# MCU-Board.net
KiCad netlist of a schematic drawn in Altium Designer
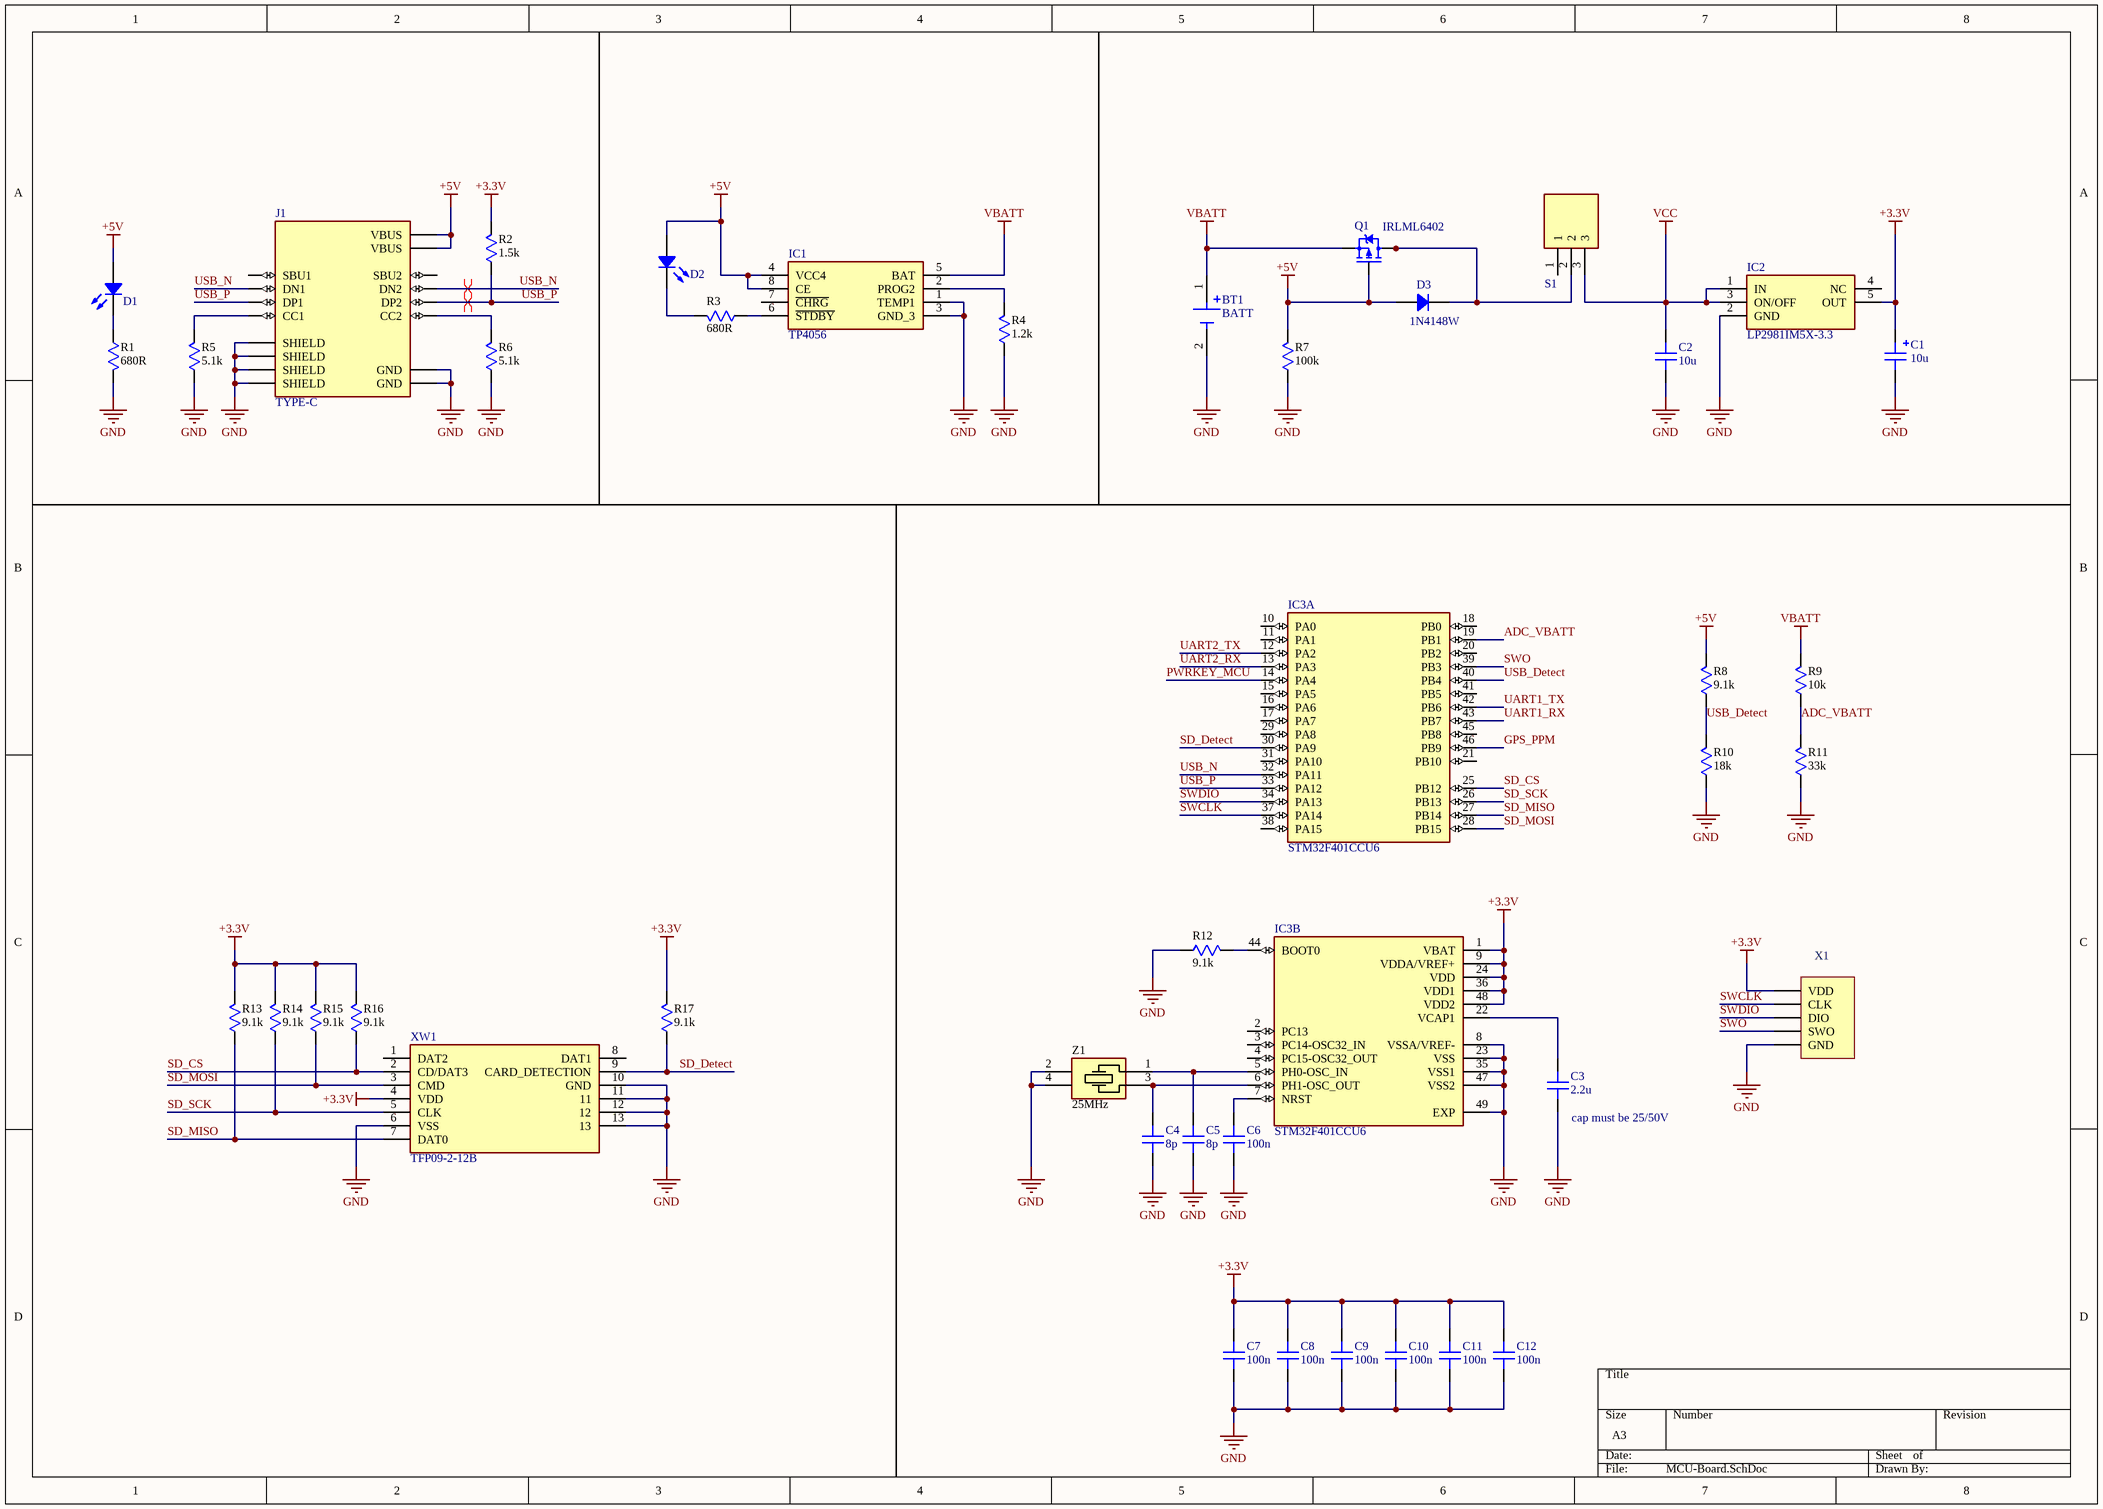
[diagram p0: MCU-Board.SchDoc]

(export (version "E")
  (design (tool "Eeschema 10.0.6"))
  (components
    (comp (ref "BT1")
      (value "BATT")
      (footprint "CON: HOLDER 18650 x1")
      (description "BATTERY")
      (fields (field (name "MP") "BH123A") (field (name "MF") "MPD"))
      (libsource (lib "Schlib") (part "BATT"))
    )
    (comp (ref "C1")
      (value "10u")
      (footprint "PcbLib:CAP: TANTAL-A")
      (description "SMD Capacitor Polar")
      (libsource (lib "Schlib") (part "Capacitor_polar"))
    )
    (comp (ref "C2")
      (value "10u")
      (footprint "PcbLib:CAP: 0805")
      (description "SMD Capacitor")
      (libsource (lib "Schlib") (part "Capacitor"))
    )
    (comp (ref "C3")
      (value "2.2u")
      (footprint "PcbLib:CAP: 0805")
      (description "SMD Capacitor")
      (libsource (lib "Schlib") (part "Capacitor"))
    )
    (comp (ref "C4")
      (value "8p")
      (footprint "PcbLib:CAP: 0603")
      (description "SMD Capacitor")
      (libsource (lib "Schlib") (part "Capacitor"))
    )
    (comp (ref "C5")
      (value "8p")
      (footprint "PcbLib:CAP: 0603")
      (description "SMD Capacitor")
      (libsource (lib "Schlib") (part "Capacitor"))
    )
    (comp (ref "C6")
      (value "100n")
      (footprint "PcbLib:CAP: 0603")
      (description "SMD Capacitor")
      (libsource (lib "Schlib") (part "Capacitor"))
    )
    (comp (ref "C7")
      (value "100n")
      (footprint "PcbLib:CAP: 0603")
      (description "SMD Capacitor")
      (libsource (lib "Schlib") (part "Capacitor"))
    )
    (comp (ref "C8")
      (value "100n")
      (footprint "PcbLib:CAP: 0603")
      (description "SMD Capacitor")
      (libsource (lib "Schlib") (part "Capacitor"))
    )
    (comp (ref "C9")
      (value "100n")
      (footprint "PcbLib:CAP: 0603")
      (description "SMD Capacitor")
      (libsource (lib "Schlib") (part "Capacitor"))
    )
    (comp (ref "C10")
      (value "100n")
      (footprint "PcbLib:CAP: 0603")
      (description "SMD Capacitor")
      (libsource (lib "Schlib") (part "Capacitor"))
    )
    (comp (ref "C11")
      (value "100n")
      (footprint "PcbLib:CAP: 0603")
      (description "SMD Capacitor")
      (libsource (lib "Schlib") (part "Capacitor"))
    )
    (comp (ref "C12")
      (value "100n")
      (footprint "PcbLib:CAP: 0603")
      (description "SMD Capacitor")
      (libsource (lib "Schlib") (part "Capacitor"))
    )
    (comp (ref "D1")
      (value "~")
      (footprint "PcbLib:LED 0603_1608")
      (description "Chip LED")
      (libsource (lib "Schlib") (part "LED"))
    )
    (comp (ref "D2")
      (value "~")
      (footprint "PcbLib:LED 0603_1608")
      (description "Chip LED")
      (libsource (lib "Schlib") (part "LED"))
    )
    (comp (ref "D3")
      (value "1N4148W")
      (footprint "DIODE: SOD123")
      (description "Rectifier Diode")
      (libsource (lib "Schlib") (part "Diode"))
    )
    (comp (ref "IC1")
      (value "TP4056")
      (footprint "PcbLib:SOIC127P600X175-9N")
      (description "Connector")
      (libsource (lib "Schlib") (part "TP4056"))
    )
    (comp (ref "IC2")
      (value "LP2981IM5X-3.3")
      (footprint "PcbLib:SOT95P280X145-5N")
      (description "Integrated Circuit")
      (fields
        (field (name "MANUFACTURER_PART_NUMBER") "LP2981IM5X-5.0")
        (field (name "MOUSER PART NUMBER") "926-LP2981IM5X-50")
      )
      (libsource (lib "Schlib") (part "LP2981IM5X-3.3"))
    )
    (comp (ref "IC3")
      (value "STM32F401CCU6")
      (footprint "PcbLib:QFN50P700X700X60-49N-D")
      (description "Integrated Circuit")
      (fields (field (name "MOUSER PART NUMBER") "511-STM32F401CCU6"))
      (libsource (lib "Schlib") (part "STM32F401CCU6"))
    )
    (comp (ref "J1")
      (value "TYPE-C")
      (footprint "PcbLib:HRO_TYPE-C-31-M-12")
      (description "USB Connectors 24 Receptacle 1 8.94*7.3mm RoHS")
      (fields (field (name "MP") "TYPE-C-31-M-12"))
      (libsource (lib "Schlib") (part "TYPE-C-31-M-12"))
    )
    (comp (ref "Q1")
      (value "IRLML6402")
      (footprint "SOT95P280X130-6N")
      (description "P-Channel Enhancement Mode MOSFET")
      (libsource (lib "Schlib") (part "MOSP_IRLMLS6802_SOT23"))
    )
    (comp (ref "R1")
      (value "680R")
      (footprint "PcbLib:RES: 0603")
      (fields
        (field (name "MANUFACTURER") "Yageo")
        (field (name "PARTNUMBER") "RC0201JR-07100RL")
        (field (name "VALUEMANUFACTURERPARTNUMBER") "Resistor film, 680R, , 0201, 0.05W, -55...+125°C")
      )
      (libsource (lib "Schlib") (part "Resistor"))
    )
    (comp (ref "R2")
      (value "1.5k")
      (footprint "PcbLib:RES: 0603")
      (fields
        (field (name "MANUFACTURER") "Yageo")
        (field (name "PARTNUMBER") "RC0201JR-07100RL")
        (field (name "VALUEMANUFACTURERPARTNUMBER") "Resistor film, 1.5k, , 0201, 0.05W, -55...+125°C")
      )
      (libsource (lib "Schlib") (part "Resistor"))
    )
    (comp (ref "R3")
      (value "680R")
      (footprint "PcbLib:RES: 0603")
      (fields
        (field (name "MANUFACTURER") "Yageo")
        (field (name "PARTNUMBER") "RC0201JR-07100RL")
        (field (name "VALUEMANUFACTURERPARTNUMBER") "Resistor film, 680R, , 0201, 0.05W, -55...+125°C")
      )
      (libsource (lib "Schlib") (part "Resistor"))
    )
    (comp (ref "R4")
      (value "1.2k")
      (footprint "PcbLib:RES: 0805")
      (fields
        (field (name "MANUFACTURER") "Yageo")
        (field (name "PARTNUMBER") "RC0201JR-07100RL")
        (field (name "VALUEMANUFACTURERPARTNUMBER") "Resistor film, 1.2k, , 0201, 0.05W, -55...+125°C")
      )
      (libsource (lib "Schlib") (part "Resistor"))
    )
    (comp (ref "R5")
      (value "5.1k")
      (footprint "PcbLib:RES: 0603")
      (fields
        (field (name "MANUFACTURER") "Yageo")
        (field (name "PARTNUMBER") "RC0201JR-07100RL")
        (field (name "VALUEMANUFACTURERPARTNUMBER") "Resistor film, 5.1k, , 0201, 0.05W, -55...+125°C")
      )
      (libsource (lib "Schlib") (part "Resistor"))
    )
    (comp (ref "R6")
      (value "5.1k")
      (footprint "PcbLib:RES: 0603")
      (fields
        (field (name "MANUFACTURER") "Yageo")
        (field (name "PARTNUMBER") "RC0201JR-07100RL")
        (field (name "VALUEMANUFACTURERPARTNUMBER") "Resistor film, 5.1k, , 0201, 0.05W, -55...+125°C")
      )
      (libsource (lib "Schlib") (part "Resistor"))
    )
    (comp (ref "R7")
      (value "100k")
      (footprint "PcbLib:RES: 0603")
      (fields
        (field (name "MANUFACTURER") "Yageo")
        (field (name "PARTNUMBER") "RC0201JR-07100RL")
        (field (name "VALUEMANUFACTURERPARTNUMBER") "Resistor film, 100k, , 0201, 0.05W, -55...+125°C")
      )
      (libsource (lib "Schlib") (part "Resistor"))
    )
    (comp (ref "R8")
      (value "9.1k")
      (footprint "PcbLib:RES: 0603")
      (fields
        (field (name "MANUFACTURER") "Yageo")
        (field (name "PARTNUMBER") "RC0201JR-07100RL")
        (field (name "VALUEMANUFACTURERPARTNUMBER") "Resistor film, 9.1k, , 0201, 0.05W, -55...+125°C")
      )
      (libsource (lib "Schlib") (part "Resistor"))
    )
    (comp (ref "R9")
      (value "10k")
      (footprint "PcbLib:RES: 0603")
      (fields
        (field (name "MANUFACTURER") "Yageo")
        (field (name "PARTNUMBER") "RC0201JR-07100RL")
        (field (name "VALUEMANUFACTURERPARTNUMBER") "Resistor film, 10k, , 0201, 0.05W, -55...+125°C")
      )
      (libsource (lib "Schlib") (part "Resistor"))
    )
    (comp (ref "R10")
      (value "18k")
      (footprint "PcbLib:RES: 0603")
      (fields
        (field (name "MANUFACTURER") "Yageo")
        (field (name "PARTNUMBER") "RC0201JR-07100RL")
        (field (name "VALUEMANUFACTURERPARTNUMBER") "Resistor film, 18k, , 0201, 0.05W, -55...+125°C")
      )
      (libsource (lib "Schlib") (part "Resistor"))
    )
    (comp (ref "R11")
      (value "33k")
      (footprint "PcbLib:RES: 0603")
      (fields
        (field (name "MANUFACTURER") "Yageo")
        (field (name "PARTNUMBER") "RC0201JR-07100RL")
        (field (name "VALUEMANUFACTURERPARTNUMBER") "Resistor film, 33k, , 0201, 0.05W, -55...+125°C")
      )
      (libsource (lib "Schlib") (part "Resistor"))
    )
    (comp (ref "R12")
      (value "9.1k")
      (footprint "PcbLib:RES: 0603")
      (fields
        (field (name "MANUFACTURER") "Yageo")
        (field (name "PARTNUMBER") "RC0201JR-07100RL")
        (field (name "VALUEMANUFACTURERPARTNUMBER") "Resistor film, 9.1k, , 0201, 0.05W, -55...+125°C")
      )
      (libsource (lib "Schlib") (part "Resistor"))
    )
    (comp (ref "R13")
      (value "9.1k")
      (footprint "PcbLib:RES: 0603")
      (fields
        (field (name "MANUFACTURER") "Yageo")
        (field (name "PARTNUMBER") "RC0201JR-07100RL")
        (field (name "VALUEMANUFACTURERPARTNUMBER") "Resistor film, 9.1k, , 0201, 0.05W, -55...+125°C")
      )
      (libsource (lib "Schlib") (part "Resistor"))
    )
    (comp (ref "R14")
      (value "9.1k")
      (footprint "PcbLib:RES: 0603")
      (fields
        (field (name "MANUFACTURER") "Yageo")
        (field (name "PARTNUMBER") "RC0201JR-07100RL")
        (field (name "VALUEMANUFACTURERPARTNUMBER") "Resistor film, 9.1k, , 0201, 0.05W, -55...+125°C")
      )
      (libsource (lib "Schlib") (part "Resistor"))
    )
    (comp (ref "R15")
      (value "9.1k")
      (footprint "PcbLib:RES: 0603")
      (fields
        (field (name "MANUFACTURER") "Yageo")
        (field (name "PARTNUMBER") "RC0201JR-07100RL")
        (field (name "VALUEMANUFACTURERPARTNUMBER") "Resistor film, 9.1k, , 0201, 0.05W, -55...+125°C")
      )
      (libsource (lib "Schlib") (part "Resistor"))
    )
    (comp (ref "R16")
      (value "9.1k")
      (footprint "PcbLib:RES: 0603")
      (fields
        (field (name "MANUFACTURER") "Yageo")
        (field (name "PARTNUMBER") "RC0201JR-07100RL")
        (field (name "VALUEMANUFACTURERPARTNUMBER") "Resistor film, 9.1k, , 0201, 0.05W, -55...+125°C")
      )
      (libsource (lib "Schlib") (part "Resistor"))
    )
    (comp (ref "R17")
      (value "9.1k")
      (footprint "PcbLib:RES: 0603")
      (fields
        (field (name "MANUFACTURER") "Yageo")
        (field (name "PARTNUMBER") "RC0201JR-07100RL")
        (field (name "VALUEMANUFACTURERPARTNUMBER") "Resistor film, 9.1k, , 0201, 0.05W, -55...+125°C")
      )
      (libsource (lib "Schlib") (part "Resistor"))
    )
    (comp (ref "S1")
      (value "OS102011MA1QN1")
      (footprint "PcbLib:OS102011MA1QN1")
      (description "Switch")
      (fields (field (name "MOUSER PART NUMBER") "611-OS102011MA1QN1"))
      (libsource (lib "Schlib") (part "OS102011MA1QN1"))
    )
    (comp (ref "X1")
      (value "~")
      (footprint "CON: PLS-4")
      (description "SWD Interface")
      (libsource (lib "Schlib") (part "Connector SWD"))
    )
    (comp (ref "XW1")
      (value "TFP09-2-12B")
      (footprint "PcbLib:TFP09212B")
      (description "Connector")
      (libsource (lib "Schlib") (part "TFP09-2-12B"))
    )
    (comp (ref "Z1")
      (value "~")
      (footprint "PcbLib:OSC: 3225")
      (fields
        (field (name "MANUFACTURER") "Murata Electronics")
        (field (name "PARTNUMBER") "XRCGB25M000F0L00R0")
        (field (name "VALUEMANUFACTURERPARTNUMBER") "Crystal, 25MHz, 6pF, ±50ppm, case 2016, -30...+85°C")
        (field (name "FREQUENCY") "25MHz")
      )
      (libsource (lib "Schlib") (part "Crystal"))
    )
  )
  (nets
    (net (code "1") (name "+3.3V") (class "Default")
      (node (ref "C1") (pin "1") (pinfunction "1_1") (pintype "passive"))
      (node (ref "C10") (pin "2") (pinfunction "2_2") (pintype "passive"))
      (node (ref "C11") (pin "2") (pinfunction "2_2") (pintype "passive"))
      (node (ref "C12") (pin "2") (pinfunction "2_2") (pintype "passive"))
      (node (ref "C7") (pin "1") (pinfunction "1_1") (pintype "passive"))
      (node (ref "C8") (pin "2") (pinfunction "2_2") (pintype "passive"))
      (node (ref "C9") (pin "2") (pinfunction "2_2") (pintype "passive"))
      (node (ref "IC2") (pin "5") (pinfunction "OUT_5") (pintype "passive"))
      (node (ref "IC3") (pin "1") (pinfunction "VBAT_1") (pintype "power_in"))
      (node (ref "IC3") (pin "24") (pinfunction "VDD_24") (pintype "power_in"))
      (node (ref "IC3") (pin "36") (pinfunction "VDD1_36") (pintype "power_in"))
      (node (ref "IC3") (pin "48") (pinfunction "VDD2_48") (pintype "power_in"))
      (node (ref "IC3") (pin "9") (pinfunction "VDDA/VREF+_9") (pintype "power_in"))
      (node (ref "R13") (pin "2") (pinfunction "2_2") (pintype "passive"))
      (node (ref "R14") (pin "2") (pinfunction "2_2") (pintype "passive"))
      (node (ref "R15") (pin "2") (pinfunction "2_2") (pintype "passive"))
      (node (ref "R16") (pin "2") (pinfunction "2_2") (pintype "passive"))
      (node (ref "R17") (pin "2") (pinfunction "2_2") (pintype "passive"))
      (node (ref "R2") (pin "2") (pinfunction "2_2") (pintype "passive"))
      (node (ref "X1") (pin "1") (pinfunction "VDD_1") (pintype "passive"))
      (node (ref "XW1") (pin "4") (pinfunction "VDD_4") (pintype "passive"))
    )
    (net (code "2") (name "+5V") (class "Default")
      (node (ref "D1") (pin "1") (pinfunction "1_1") (pintype "passive"))
      (node (ref "D2") (pin "1") (pinfunction "1_1") (pintype "passive"))
      (node (ref "D3") (pin "1") (pinfunction "1_1") (pintype "passive"))
      (node (ref "IC1") (pin "4") (pinfunction "VCC4_4") (pintype "passive"))
      (node (ref "IC1") (pin "8") (pinfunction "CE_8") (pintype "passive"))
      (node (ref "J1") (pin "A4B9") (pinfunction "VBUS_A4B9") (pintype "power_in"))
      (node (ref "J1") (pin "B4A9") (pinfunction "VBUS_B4A9") (pintype "power_in"))
      (node (ref "Q1") (pin "3") (pinfunction "G_3") (pintype "passive"))
      (node (ref "R7") (pin "2") (pinfunction "2_2") (pintype "passive"))
      (node (ref "R8") (pin "2") (pinfunction "2_2") (pintype "passive"))
    )
    (net (code "3") (name "/ADC_VBATT") (class "Default")
      (node (ref "IC3") (pin "19") (pinfunction "PB1_19") (pintype "bidirectional"))
      (node (ref "R11") (pin "2") (pinfunction "2_2") (pintype "passive"))
      (node (ref "R9") (pin "1") (pinfunction "1_1") (pintype "passive"))
    )
    (net (code "4") (name "/GPS_PPM") (class "Default")
      (node (ref "IC3") (pin "46") (pinfunction "PB9_46") (pintype "bidirectional"))
    )
    (net (code "5") (name "/PWRKEY_MCU") (class "Default")
      (node (ref "IC3") (pin "14") (pinfunction "PA4_14") (pintype "bidirectional"))
    )
    (net (code "6") (name "/SD_CS") (class "Default")
      (node (ref "IC3") (pin "25") (pinfunction "PB12_25") (pintype "bidirectional"))
      (node (ref "R16") (pin "1") (pinfunction "1_1") (pintype "passive"))
      (node (ref "XW1") (pin "2") (pinfunction "CD/DAT3_2") (pintype "passive"))
    )
    (net (code "7") (name "/SD_Detect") (class "Default")
      (node (ref "IC3") (pin "30") (pinfunction "PA9_30") (pintype "bidirectional"))
      (node (ref "R17") (pin "1") (pinfunction "1_1") (pintype "passive"))
      (node (ref "XW1") (pin "9") (pinfunction "CARD_DETECTION_9") (pintype "passive"))
    )
    (net (code "8") (name "/SD_MISO") (class "Default")
      (node (ref "IC3") (pin "27") (pinfunction "PB14_27") (pintype "bidirectional"))
      (node (ref "R13") (pin "1") (pinfunction "1_1") (pintype "passive"))
      (node (ref "XW1") (pin "7") (pinfunction "DAT0_7") (pintype "passive"))
    )
    (net (code "9") (name "/SD_MOSI") (class "Default")
      (node (ref "IC3") (pin "28") (pinfunction "PB15_28") (pintype "bidirectional"))
      (node (ref "R15") (pin "1") (pinfunction "1_1") (pintype "passive"))
      (node (ref "XW1") (pin "3") (pinfunction "CMD_3") (pintype "passive"))
    )
    (net (code "10") (name "/SD_SCK") (class "Default")
      (node (ref "IC3") (pin "26") (pinfunction "PB13_26") (pintype "bidirectional"))
      (node (ref "R14") (pin "1") (pinfunction "1_1") (pintype "passive"))
      (node (ref "XW1") (pin "5") (pinfunction "CLK_5") (pintype "passive"))
    )
    (net (code "11") (name "/SWCLK") (class "Default")
      (node (ref "IC3") (pin "37") (pinfunction "PA14_37") (pintype "bidirectional"))
      (node (ref "X1") (pin "2") (pinfunction "CLK_2") (pintype "passive"))
    )
    (net (code "12") (name "/SWDIO") (class "Default")
      (node (ref "IC3") (pin "34") (pinfunction "PA13_34") (pintype "bidirectional"))
      (node (ref "X1") (pin "4") (pinfunction "DIO_4") (pintype "passive"))
    )
    (net (code "13") (name "/SWO") (class "Default")
      (node (ref "IC3") (pin "39") (pinfunction "PB3_39") (pintype "bidirectional"))
      (node (ref "X1") (pin "5") (pinfunction "SWO_5") (pintype "passive"))
    )
    (net (code "14") (name "/UART1_RX") (class "Default")
      (node (ref "IC3") (pin "43") (pinfunction "PB7_43") (pintype "bidirectional"))
    )
    (net (code "15") (name "/UART1_TX") (class "Default")
      (node (ref "IC3") (pin "42") (pinfunction "PB6_42") (pintype "bidirectional"))
    )
    (net (code "16") (name "/UART2_RX") (class "Default")
      (node (ref "IC3") (pin "13") (pinfunction "PA3_13") (pintype "bidirectional"))
    )
    (net (code "17") (name "/UART2_TX") (class "Default")
      (node (ref "IC3") (pin "12") (pinfunction "PA2_12") (pintype "bidirectional"))
    )
    (net (code "18") (name "/USB_Detect") (class "Default")
      (node (ref "IC3") (pin "40") (pinfunction "PB4_40") (pintype "bidirectional"))
      (node (ref "R10") (pin "2") (pinfunction "2_2") (pintype "passive"))
      (node (ref "R8") (pin "1") (pinfunction "1_1") (pintype "passive"))
    )
    (net (code "19") (name "/USB_N") (class "Default")
      (node (ref "IC3") (pin "32") (pinfunction "PA11_32") (pintype "bidirectional"))
      (node (ref "J1") (pin "A7") (pinfunction "DN1_A7") (pintype "bidirectional"))
      (node (ref "J1") (pin "B7") (pinfunction "DN2_B7") (pintype "bidirectional"))
    )
    (net (code "20") (name "/USB_P") (class "Default")
      (node (ref "IC3") (pin "33") (pinfunction "PA12_33") (pintype "bidirectional"))
      (node (ref "J1") (pin "A6") (pinfunction "DP1_A6") (pintype "bidirectional"))
      (node (ref "J1") (pin "B6") (pinfunction "DP2_B6") (pintype "bidirectional"))
      (node (ref "R2") (pin "1") (pinfunction "1_1") (pintype "passive"))
    )
    (net (code "21") (name "GND") (class "Default")
      (node (ref "BT1") (pin "2") (pinfunction "NEG_2") (pintype "passive"))
      (node (ref "C1") (pin "2") (pinfunction "2_2") (pintype "passive"))
      (node (ref "C10") (pin "1") (pinfunction "1_1") (pintype "passive"))
      (node (ref "C11") (pin "1") (pinfunction "1_1") (pintype "passive"))
      (node (ref "C12") (pin "1") (pinfunction "1_1") (pintype "passive"))
      (node (ref "C2") (pin "1") (pinfunction "1_1") (pintype "passive"))
      (node (ref "C3") (pin "1") (pinfunction "1_1") (pintype "passive"))
      (node (ref "C4") (pin "1") (pinfunction "1_1") (pintype "passive"))
      (node (ref "C5") (pin "2") (pinfunction "2_2") (pintype "passive"))
      (node (ref "C6") (pin "1") (pinfunction "1_1") (pintype "passive"))
      (node (ref "C7") (pin "2") (pinfunction "2_2") (pintype "passive"))
      (node (ref "C8") (pin "1") (pinfunction "1_1") (pintype "passive"))
      (node (ref "C9") (pin "1") (pinfunction "1_1") (pintype "passive"))
      (node (ref "IC1") (pin "1") (pinfunction "TEMP1_1") (pintype "passive"))
      (node (ref "IC1") (pin "3") (pinfunction "GND_3_3") (pintype "passive"))
      (node (ref "IC2") (pin "2") (pinfunction "GND_2") (pintype "passive"))
      (node (ref "IC3") (pin "23") (pinfunction "VSS_23") (pintype "power_in"))
      (node (ref "IC3") (pin "35") (pinfunction "VSS1_35") (pintype "power_in"))
      (node (ref "IC3") (pin "47") (pinfunction "VSS2_47") (pintype "power_in"))
      (node (ref "IC3") (pin "49") (pinfunction "EXP_49") (pintype "power_in"))
      (node (ref "IC3") (pin "8") (pinfunction "VSSA/VREF-_8") (pintype "power_in"))
      (node (ref "J1") (pin "A1B12") (pinfunction "GND_A1B12") (pintype "power_in"))
      (node (ref "J1") (pin "B1A12") (pinfunction "GND_B1A12") (pintype "power_in"))
      (node (ref "J1") (pin "S1") (pinfunction "SHIELD_S1") (pintype "passive"))
      (node (ref "J1") (pin "S2") (pinfunction "SHIELD_S2") (pintype "passive"))
      (node (ref "J1") (pin "S3") (pinfunction "SHIELD_S3") (pintype "passive"))
      (node (ref "J1") (pin "S4") (pinfunction "SHIELD_S4") (pintype "passive"))
      (node (ref "R1") (pin "2") (pinfunction "2_2") (pintype "passive"))
      (node (ref "R10") (pin "1") (pinfunction "1_1") (pintype "passive"))
      (node (ref "R11") (pin "1") (pinfunction "1_1") (pintype "passive"))
      (node (ref "R12") (pin "1") (pinfunction "1_1") (pintype "passive"))
      (node (ref "R4") (pin "1") (pinfunction "1_1") (pintype "passive"))
      (node (ref "R5") (pin "1") (pinfunction "1_1") (pintype "passive"))
      (node (ref "R6") (pin "1") (pinfunction "1_1") (pintype "passive"))
      (node (ref "R7") (pin "1") (pinfunction "1_1") (pintype "passive"))
      (node (ref "X1") (pin "3") (pinfunction "GND_3") (pintype "passive"))
      (node (ref "XW1") (pin "10") (pinfunction "GND_10") (pintype "passive"))
      (node (ref "XW1") (pin "11") (pinfunction "11_11") (pintype "passive"))
      (node (ref "XW1") (pin "12") (pinfunction "12_12") (pintype "passive"))
      (node (ref "XW1") (pin "13") (pinfunction "13_13") (pintype "passive"))
      (node (ref "XW1") (pin "6") (pinfunction "VSS_6") (pintype "passive"))
      (node (ref "Z1") (pin "2") (pinfunction "2_2") (pintype "passive"))
      (node (ref "Z1") (pin "4") (pinfunction "4_4") (pintype "passive"))
    )
    (net (code "22") (name "Net-(D1-Pad2)") (class "Default")
      (node (ref "D1") (pin "2") (pinfunction "2_2") (pintype "passive"))
      (node (ref "R1") (pin "1") (pinfunction "1_1") (pintype "passive"))
    )
    (net (code "23") (name "Net-(D2-Pad2)") (class "Default")
      (node (ref "D2") (pin "2") (pinfunction "2_2") (pintype "passive"))
      (node (ref "R3") (pin "2") (pinfunction "2_2") (pintype "passive"))
    )
    (net (code "24") (name "Net-(D3-Pad2)") (class "Default")
      (node (ref "D3") (pin "2") (pinfunction "2_2") (pintype "passive"))
      (node (ref "Q1") (pin "1") (pinfunction "D_1") (pintype "passive"))
      (node (ref "Q1") (pin "2") (pinfunction "D_2") (pintype "passive"))
      (node (ref "Q1") (pin "5") (pinfunction "D_5") (pintype "passive"))
      (node (ref "Q1") (pin "6") (pinfunction "D_6") (pintype "passive"))
      (node (ref "S1") (pin "2") (pinfunction "2_2") (pintype "passive"))
    )
    (net (code "25") (name "Net-(IC1-PROG2)") (class "Default")
      (node (ref "IC1") (pin "2") (pinfunction "PROG2_2") (pintype "passive"))
      (node (ref "R4") (pin "2") (pinfunction "2_2") (pintype "passive"))
    )
    (net (code "26") (name "Net-(IC1-~{STDBY})") (class "Default")
      (node (ref "IC1") (pin "6") (pinfunction "~{STDBY}_6") (pintype "passive"))
      (node (ref "R3") (pin "1") (pinfunction "1_1") (pintype "passive"))
    )
    (net (code "27") (name "Net-(IC3B-BOOT0)") (class "Default")
      (node (ref "IC3") (pin "44") (pinfunction "BOOT0_44") (pintype "bidirectional"))
      (node (ref "R12") (pin "2") (pinfunction "2_2") (pintype "passive"))
    )
    (net (code "28") (name "Net-(IC3B-NRST)") (class "Default")
      (node (ref "C6") (pin "2") (pinfunction "2_2") (pintype "passive"))
      (node (ref "IC3") (pin "7") (pinfunction "NRST_7") (pintype "bidirectional"))
    )
    (net (code "29") (name "Net-(IC3B-PH0-OSC_IN)") (class "Default")
      (node (ref "C5") (pin "1") (pinfunction "1_1") (pintype "passive"))
      (node (ref "IC3") (pin "5") (pinfunction "PH0-OSC_IN_5") (pintype "bidirectional"))
      (node (ref "Z1") (pin "1") (pinfunction "1_1") (pintype "passive"))
    )
    (net (code "30") (name "Net-(IC3B-PH1-OSC_OUT)") (class "Default")
      (node (ref "C4") (pin "2") (pinfunction "2_2") (pintype "passive"))
      (node (ref "IC3") (pin "6") (pinfunction "PH1-OSC_OUT_6") (pintype "bidirectional"))
      (node (ref "Z1") (pin "3") (pinfunction "3_3") (pintype "passive"))
    )
    (net (code "31") (name "Net-(IC3B-VCAP1)") (class "Default")
      (node (ref "C3") (pin "2") (pinfunction "2_2") (pintype "passive"))
      (node (ref "IC3") (pin "22") (pinfunction "VCAP1_22") (pintype "power_in"))
    )
    (net (code "32") (name "Net-(J1-CC1)") (class "Default")
      (node (ref "J1") (pin "A5") (pinfunction "CC1_A5") (pintype "bidirectional"))
      (node (ref "R5") (pin "2") (pinfunction "2_2") (pintype "passive"))
    )
    (net (code "33") (name "Net-(J1-CC2)") (class "Default")
      (node (ref "J1") (pin "B5") (pinfunction "CC2_B5") (pintype "bidirectional"))
      (node (ref "R6") (pin "2") (pinfunction "2_2") (pintype "passive"))
    )
    (net (code "34") (name "VBATT") (class "Default")
      (node (ref "BT1") (pin "1") (pinfunction "POS_1") (pintype "passive"))
      (node (ref "IC1") (pin "5") (pinfunction "BAT_5") (pintype "passive"))
      (node (ref "Q1") (pin "4") (pinfunction "S_4") (pintype "passive"))
      (node (ref "R9") (pin "2") (pinfunction "2_2") (pintype "passive"))
    )
    (net (code "35") (name "VCC") (class "Default")
      (node (ref "C2") (pin "2") (pinfunction "2_2") (pintype "passive"))
      (node (ref "IC2") (pin "1") (pinfunction "IN_1") (pintype "passive"))
      (node (ref "IC2") (pin "3") (pinfunction "ON/OFF_3") (pintype "passive"))
      (node (ref "S1") (pin "3") (pinfunction "3_3") (pintype "passive"))
    )
    (net (code "36") (name "unconnected-(IC1-~{CHRG}-Pad7)") (class "Default")
      (node (ref "IC1") (pin "7") (pinfunction "~{CHRG}_7") (pintype "passive"))
    )
    (net (code "37") (name "unconnected-(IC2-NC-Pad4)") (class "Default")
      (node (ref "IC2") (pin "4") (pinfunction "NC_4") (pintype "passive"))
    )
    (net (code "38") (name "unconnected-(IC3A-PA0-Pad10)") (class "Default")
      (node (ref "IC3") (pin "10") (pinfunction "PA0_10") (pintype "bidirectional"))
    )
    (net (code "39") (name "unconnected-(IC3A-PA1-Pad11)") (class "Default")
      (node (ref "IC3") (pin "11") (pinfunction "PA1_11") (pintype "bidirectional"))
    )
    (net (code "40") (name "unconnected-(IC3A-PA5-Pad15)") (class "Default")
      (node (ref "IC3") (pin "15") (pinfunction "PA5_15") (pintype "bidirectional"))
    )
    (net (code "41") (name "unconnected-(IC3A-PA6-Pad16)") (class "Default")
      (node (ref "IC3") (pin "16") (pinfunction "PA6_16") (pintype "bidirectional"))
    )
    (net (code "42") (name "unconnected-(IC3A-PA7-Pad17)") (class "Default")
      (node (ref "IC3") (pin "17") (pinfunction "PA7_17") (pintype "bidirectional"))
    )
    (net (code "43") (name "unconnected-(IC3A-PA8-Pad29)") (class "Default")
      (node (ref "IC3") (pin "29") (pinfunction "PA8_29") (pintype "bidirectional"))
    )
    (net (code "44") (name "unconnected-(IC3A-PA10-Pad31)") (class "Default")
      (node (ref "IC3") (pin "31") (pinfunction "PA10_31") (pintype "bidirectional"))
    )
    (net (code "45") (name "unconnected-(IC3A-PA15-Pad38)") (class "Default")
      (node (ref "IC3") (pin "38") (pinfunction "PA15_38") (pintype "bidirectional"))
    )
    (net (code "46") (name "unconnected-(IC3A-PB0-Pad18)") (class "Default")
      (node (ref "IC3") (pin "18") (pinfunction "PB0_18") (pintype "bidirectional"))
    )
    (net (code "47") (name "unconnected-(IC3A-PB2-Pad20)") (class "Default")
      (node (ref "IC3") (pin "20") (pinfunction "PB2_20") (pintype "bidirectional"))
    )
    (net (code "48") (name "unconnected-(IC3A-PB5-Pad41)") (class "Default")
      (node (ref "IC3") (pin "41") (pinfunction "PB5_41") (pintype "bidirectional"))
    )
    (net (code "49") (name "unconnected-(IC3A-PB8-Pad45)") (class "Default")
      (node (ref "IC3") (pin "45") (pinfunction "PB8_45") (pintype "bidirectional"))
    )
    (net (code "50") (name "unconnected-(IC3A-PB10-Pad21)") (class "Default")
      (node (ref "IC3") (pin "21") (pinfunction "PB10_21") (pintype "bidirectional"))
    )
    (net (code "51") (name "unconnected-(IC3B-PC13-Pad2)") (class "Default")
      (node (ref "IC3") (pin "2") (pinfunction "PC13_2") (pintype "bidirectional"))
    )
    (net (code "52") (name "unconnected-(IC3B-PC14-OSC32_IN-Pad3)") (class "Default")
      (node (ref "IC3") (pin "3") (pinfunction "PC14-OSC32_IN_3") (pintype "bidirectional"))
    )
    (net (code "53") (name "unconnected-(IC3B-PC15-OSC32_OUT-Pad4)") (class "Default")
      (node (ref "IC3") (pin "4") (pinfunction "PC15-OSC32_OUT_4") (pintype "bidirectional"))
    )
    (net (code "54") (name "unconnected-(J1-SBU1-PadA8)") (class "Default")
      (node (ref "J1") (pin "A8") (pinfunction "SBU1_A8") (pintype "bidirectional"))
    )
    (net (code "55") (name "unconnected-(J1-SBU2-PadB8)") (class "Default")
      (node (ref "J1") (pin "B8") (pinfunction "SBU2_B8") (pintype "bidirectional"))
    )
    (net (code "56") (name "unconnected-(S1-Pad1)") (class "Default")
      (node (ref "S1") (pin "1") (pinfunction "1_1") (pintype "passive"))
    )
    (net (code "57") (name "unconnected-(XW1-DAT1-Pad8)") (class "Default")
      (node (ref "XW1") (pin "8") (pinfunction "DAT1_8") (pintype "passive"))
    )
    (net (code "58") (name "unconnected-(XW1-DAT2-Pad1)") (class "Default")
      (node (ref "XW1") (pin "1") (pinfunction "DAT2_1") (pintype "passive"))
    )
  )
)
